# load_cell_amp.net
KiCad netlist of a schematic drawn in Altium Designer
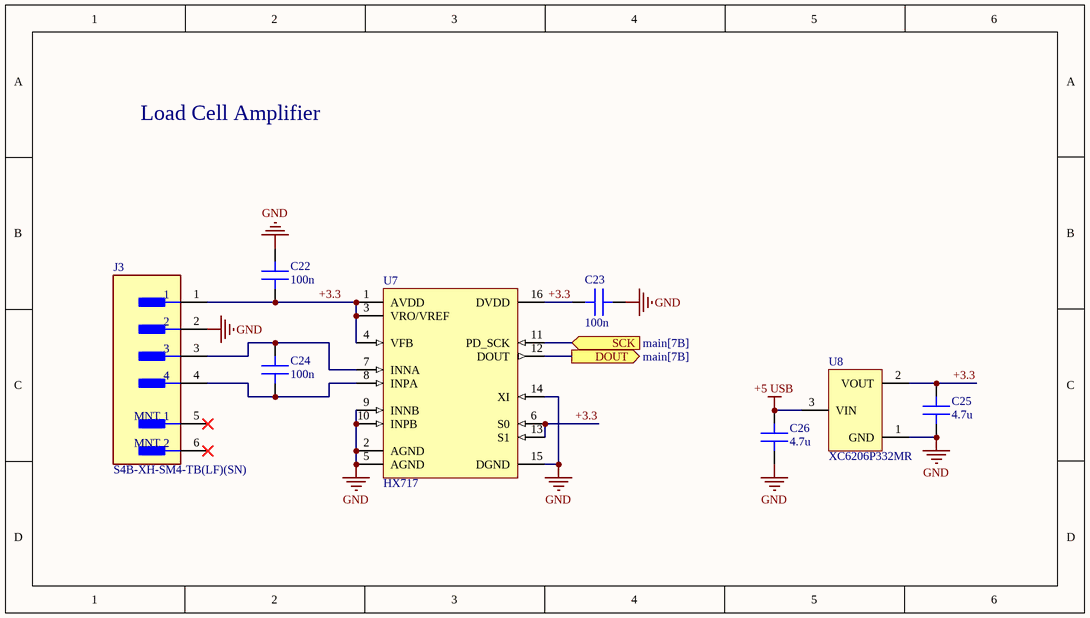
[diagram p0: load cell amp.SchDoc]

(export (version "E")
  (design (tool "Eeschema 10.0.6"))
  (components
    (comp (ref "C22")
      (value "100n")
      (footprint "IPC C C0402 NO SILK")
      (libsource (lib "JLCPCB Library") (part "Generic CAP 0402"))
    )
    (comp (ref "C23")
      (value "100n")
      (footprint "IPC C C0402 NO SILK")
      (libsource (lib "JLCPCB Library") (part "Generic CAP 0402"))
    )
    (comp (ref "C24")
      (value "100n")
      (footprint "IPC C C0402 NO SILK")
      (libsource (lib "JLCPCB Library") (part "Generic CAP 0402"))
    )
    (comp (ref "C25")
      (value "4.7u")
      (footprint "IPC C C0603 NO SILK")
      (libsource (lib "JLCPCB Library") (part "Generic CAP 0603"))
    )
    (comp (ref "C26")
      (value "4.7u")
      (footprint "IPC C C0603 NO SILK")
      (libsource (lib "JLCPCB Library") (part "Generic CAP 0603"))
    )
    (comp (ref "J3")
      (value "S4B-XH-SM4-TB(LF)(SN)")
      (footprint "FP-S4B-XH-SM4-TB_LF_SN-MFG")
      (description "CONN HEADER SMD R/A 4POS 2.5MM")
      (libsource (lib "Altium Content Vault") (part "a9f55b2ccc20dccd0fcbea9c396e26a"))
    )
    (comp (ref "U7")
      (value "HX717")
      (footprint "SOIC127P600X160-16L")
      (libsource (lib "JLCPCB Library") (part "HX717"))
    )
    (comp (ref "U8")
      (value "XC6206P332MR")
      (footprint "SOT23-3")
      (fields (field (name "MANUFACTURER") "TOREX(特瑞仕)"))
      (libsource (lib "JLCPCB Library") (part "3.3V Regulator XC6206P332MR_C5446"))
    )
  )
  (nets
    (net (code "1") (name "+5 USB") (class "Default")
      (node (ref "C26") (pin "2") (pinfunction "2_2") (pintype "passive"))
      (node (ref "U8") (pin "3") (pinfunction "VIN_3") (pintype "power_in"))
    )
    (net (code "2") (name "/+3.3") (class "Default")
      (node (ref "C22") (pin "1") (pinfunction "1_1") (pintype "passive"))
      (node (ref "C23") (pin "2") (pinfunction "2_2") (pintype "passive"))
      (node (ref "C25") (pin "2") (pinfunction "2_2") (pintype "passive"))
      (node (ref "J3") (pin "1") (pinfunction "1_1") (pintype "passive"))
      (node (ref "U7") (pin "1") (pinfunction "AVDD_1") (pintype "power_in"))
      (node (ref "U7") (pin "13") (pinfunction "S1_13") (pintype "input"))
      (node (ref "U7") (pin "16") (pinfunction "DVDD_16") (pintype "power_in"))
      (node (ref "U7") (pin "3") (pinfunction "VRO/VREF_3") (pintype "passive"))
      (node (ref "U7") (pin "4") (pinfunction "VFB_4") (pintype "input"))
      (node (ref "U7") (pin "6") (pinfunction "S0_6") (pintype "input"))
      (node (ref "U8") (pin "2") (pinfunction "VOUT_2") (pintype "power_in"))
    )
    (net (code "3") (name "/DOUT") (class "Default")
      (node (ref "U7") (pin "12") (pinfunction "DOUT_12") (pintype "output"))
    )
    (net (code "4") (name "/SCK") (class "Default")
      (node (ref "U7") (pin "11") (pinfunction "PD_SCK_11") (pintype "input"))
    )
    (net (code "5") (name "GND") (class "Default")
      (node (ref "C22") (pin "2") (pinfunction "2_2") (pintype "passive"))
      (node (ref "C23") (pin "1") (pinfunction "1_1") (pintype "passive"))
      (node (ref "C25") (pin "1") (pinfunction "1_1") (pintype "passive"))
      (node (ref "C26") (pin "1") (pinfunction "1_1") (pintype "passive"))
      (node (ref "J3") (pin "2") (pinfunction "2_2") (pintype "passive"))
      (node (ref "U7") (pin "10") (pinfunction "INPB_10") (pintype "input"))
      (node (ref "U7") (pin "14") (pinfunction "XI_14") (pintype "input"))
      (node (ref "U7") (pin "15") (pinfunction "DGND_15") (pintype "power_in"))
      (node (ref "U7") (pin "2") (pinfunction "AGND_2") (pintype "power_in"))
      (node (ref "U7") (pin "5") (pinfunction "AGND_5") (pintype "power_in"))
      (node (ref "U7") (pin "9") (pinfunction "INNB_9") (pintype "input"))
      (node (ref "U8") (pin "1") (pinfunction "GND_1") (pintype "power_in"))
    )
    (net (code "6") (name "Net-(U7-INNA)") (class "Default")
      (node (ref "C24") (pin "2") (pinfunction "2_2") (pintype "passive"))
      (node (ref "J3") (pin "3") (pinfunction "3_3") (pintype "passive"))
      (node (ref "U7") (pin "7") (pinfunction "INNA_7") (pintype "input"))
    )
    (net (code "7") (name "Net-(U7-INPA)") (class "Default")
      (node (ref "C24") (pin "1") (pinfunction "1_1") (pintype "passive"))
      (node (ref "J3") (pin "4") (pinfunction "4_4") (pintype "passive"))
      (node (ref "U7") (pin "8") (pinfunction "INPA_8") (pintype "input"))
    )
    (net (code "8") (name "unconnected-(J3-MNT_1-Pad5)") (class "Default")
      (node (ref "J3") (pin "5") (pinfunction "MNT_1_5") (pintype "passive+no_connect"))
    )
    (net (code "9") (name "unconnected-(J3-MNT_2-Pad6)") (class "Default")
      (node (ref "J3") (pin "6") (pinfunction "MNT_2_6") (pintype "passive+no_connect"))
    )
  )
)
